# DB_Sensors-X02.net
KiCad netlist of a schematic drawn in Altium Designer
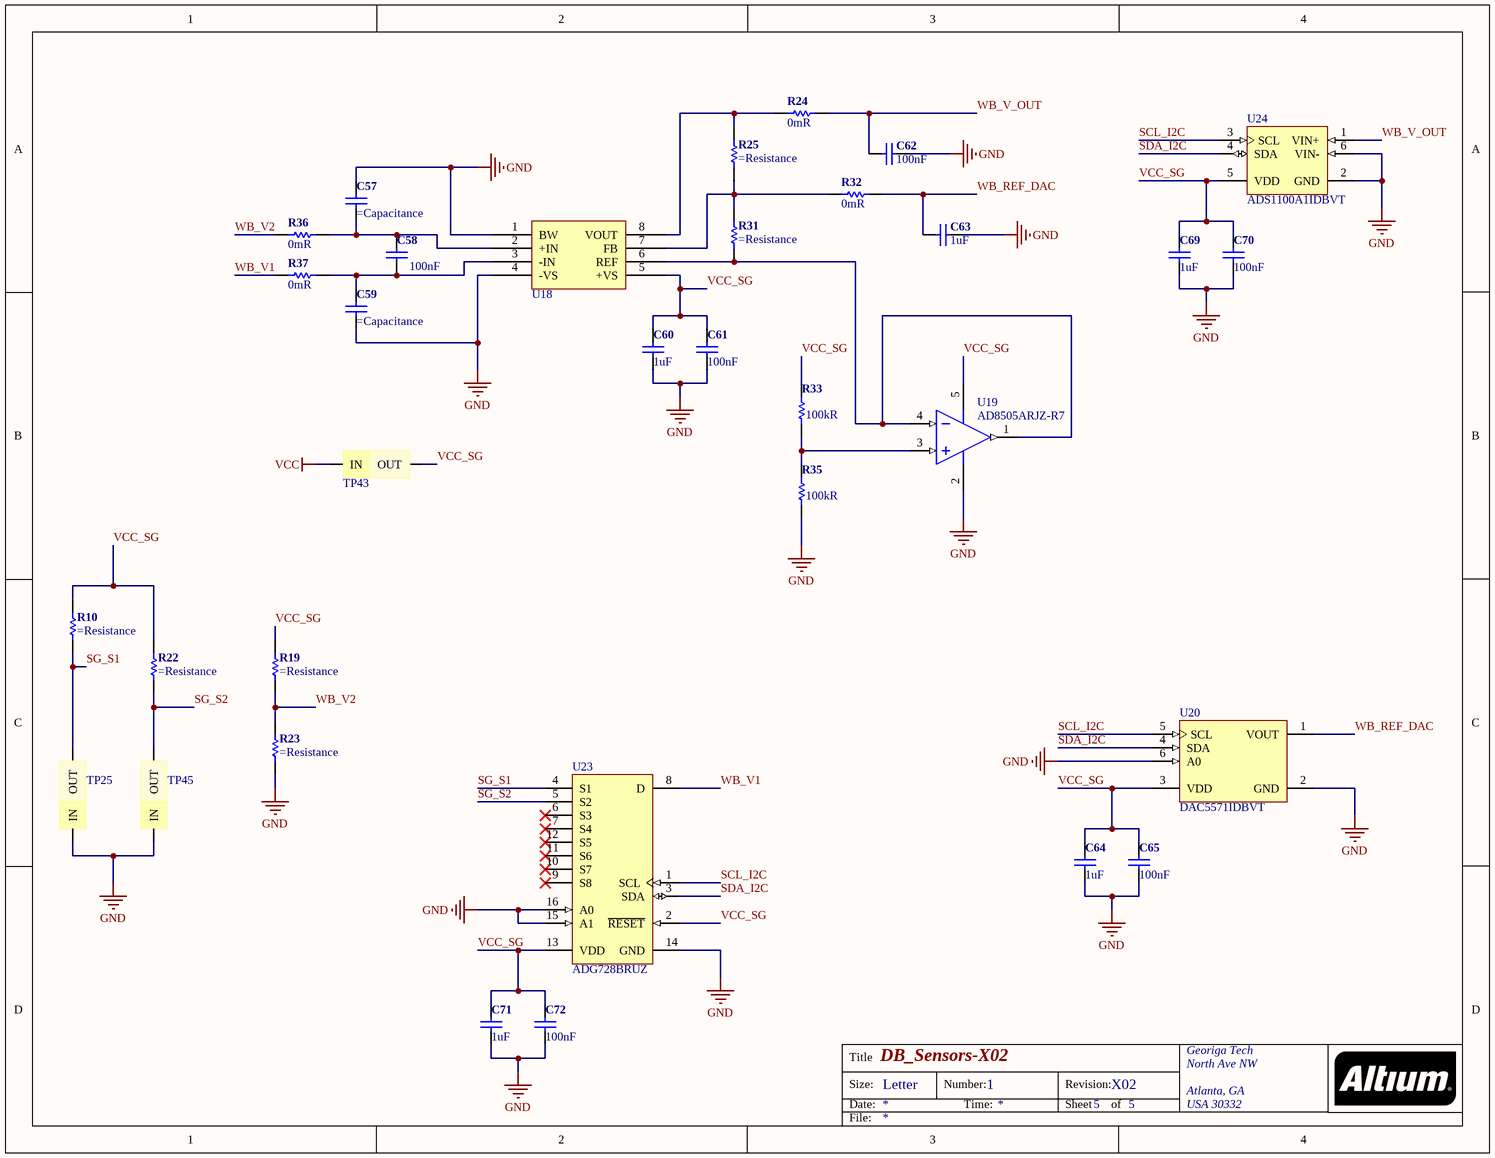
[diagram p0: DB_Sensors-X02.SchDoc]

(export (version "E")
  (design (tool "Eeschema 10.0.6"))
  (components
    (comp (ref "C57")
      (value "~")
      (footprint "C0402")
      (description "___ OHM ___ mW 0402(1005) SMD")
      (libsource (lib "DB-X02") (part "C-0402(1005)"))
    )
    (comp (ref "C58")
      (value "100nF")
      (footprint "C0402")
      (fields
        (field (name "MANUFACTURER") "Taiyo Yuden")
        (field (name "MANUFACTURER PART NUMBER") "TMK105BJ104KV-F")
        (field (name "TOLERANCE") "10%")
      )
      (libsource (lib "DB-X02") (part "C-0402(1005)"))
    )
    (comp (ref "C59")
      (value "~")
      (footprint "C0402")
      (description "___ OHM ___ mW 0402(1005) SMD")
      (libsource (lib "DB-X02") (part "C-0402(1005)"))
    )
    (comp (ref "C60")
      (value "1uF")
      (footprint "C0402")
      (fields
        (field (name "MANUFACTURER") "Yageo")
        (field (name "MANUFACTURER PART NUMBER") "CC0402MRX5R5BB105")
        (field (name "TOLERANCE") "20%")
      )
      (libsource (lib "DB-X02") (part "C-0402(1005)"))
    )
    (comp (ref "C61")
      (value "100nF")
      (footprint "C0402")
      (fields
        (field (name "MANUFACTURER") "Taiyo Yuden")
        (field (name "MANUFACTURER PART NUMBER") "TMK105BJ104KV-F")
        (field (name "TOLERANCE") "10%")
      )
      (libsource (lib "DB-X02") (part "C-0402(1005)"))
    )
    (comp (ref "C62")
      (value "100nF")
      (footprint "C0402")
      (fields
        (field (name "MANUFACTURER") "Taiyo Yuden")
        (field (name "MANUFACTURER PART NUMBER") "TMK105BJ104KV-F")
        (field (name "TOLERANCE") "10%")
      )
      (libsource (lib "DB-X02") (part "C-0402(1005)"))
    )
    (comp (ref "C63")
      (value "1uF")
      (footprint "C0402")
      (fields
        (field (name "MANUFACTURER") "Yageo")
        (field (name "MANUFACTURER PART NUMBER") "CC0402MRX5R5BB105")
        (field (name "TOLERANCE") "20%")
      )
      (libsource (lib "DB-X02") (part "C-0402(1005)"))
    )
    (comp (ref "C64")
      (value "1uF")
      (footprint "C0402")
      (fields
        (field (name "MANUFACTURER") "Yageo")
        (field (name "MANUFACTURER PART NUMBER") "CC0402MRX5R5BB105")
        (field (name "TOLERANCE") "20%")
      )
      (libsource (lib "DB-X02") (part "C-0402(1005)"))
    )
    (comp (ref "C65")
      (value "100nF")
      (footprint "C0402")
      (fields
        (field (name "MANUFACTURER") "Taiyo Yuden")
        (field (name "MANUFACTURER PART NUMBER") "TMK105BJ104KV-F")
        (field (name "TOLERANCE") "10%")
      )
      (libsource (lib "DB-X02") (part "C-0402(1005)"))
    )
    (comp (ref "C69")
      (value "1uF")
      (footprint "C0402")
      (fields
        (field (name "MANUFACTURER") "Yageo")
        (field (name "MANUFACTURER PART NUMBER") "CC0402MRX5R5BB105")
        (field (name "TOLERANCE") "20%")
      )
      (libsource (lib "DB-X02") (part "C-0402(1005)"))
    )
    (comp (ref "C70")
      (value "100nF")
      (footprint "C0402")
      (fields
        (field (name "MANUFACTURER") "Taiyo Yuden")
        (field (name "MANUFACTURER PART NUMBER") "TMK105BJ104KV-F")
        (field (name "TOLERANCE") "10%")
      )
      (libsource (lib "DB-X02") (part "C-0402(1005)"))
    )
    (comp (ref "C71")
      (value "1uF")
      (footprint "C0402")
      (fields
        (field (name "MANUFACTURER") "Yageo")
        (field (name "MANUFACTURER PART NUMBER") "CC0402MRX5R5BB105")
        (field (name "TOLERANCE") "20%")
      )
      (libsource (lib "DB-X02") (part "C-0402(1005)"))
    )
    (comp (ref "C72")
      (value "100nF")
      (footprint "C0402")
      (fields
        (field (name "MANUFACTURER") "Taiyo Yuden")
        (field (name "MANUFACTURER PART NUMBER") "TMK105BJ104KV-F")
        (field (name "TOLERANCE") "10%")
      )
      (libsource (lib "DB-X02") (part "C-0402(1005)"))
    )
    (comp (ref "R10")
      (value "~")
      (footprint "R0402")
      (description "___ OHM ___ mW 0402(1005) SMD")
      (libsource (lib "DB-X02") (part "R-0402(1005)"))
    )
    (comp (ref "R19")
      (value "~")
      (footprint "R0402")
      (description "___ OHM ___ mW 0402(1005) SMD")
      (libsource (lib "DB-X02") (part "R-0402(1005)"))
    )
    (comp (ref "R22")
      (value "~")
      (footprint "R0402")
      (description "___ OHM ___ mW 0402(1005) SMD")
      (libsource (lib "DB-X02") (part "R-0402(1005)"))
    )
    (comp (ref "R23")
      (value "~")
      (footprint "R0402")
      (description "___ OHM ___ mW 0402(1005) SMD")
      (libsource (lib "DB-X02") (part "R-0402(1005)"))
    )
    (comp (ref "R24")
      (value "0mR")
      (footprint "R0402")
      (description "Fixed Resistor, Metal Glaze/thick Film, 0.0625W, 0ohm, Surface Mount, 0402")
      (fields
        (field (name "MANUFACTURER") "Yageo")
        (field (name "MANUFACTURER PART NUMBER") "AC0402JR-070RL")
      )
      (libsource (lib "DB-X02") (part "R-0402(1005)"))
    )
    (comp (ref "R25")
      (value "~")
      (footprint "R0402")
      (description "___ OHM ___ mW 0402(1005) SMD")
      (libsource (lib "DB-X02") (part "R-0402(1005)"))
    )
    (comp (ref "R31")
      (value "~")
      (footprint "R0402")
      (description "___ OHM ___ mW 0402(1005) SMD")
      (libsource (lib "DB-X02") (part "R-0402(1005)"))
    )
    (comp (ref "R32")
      (value "0mR")
      (footprint "R0402")
      (description "Fixed Resistor, Metal Glaze/thick Film, 0.0625W, 0ohm, Surface Mount, 0402")
      (fields
        (field (name "MANUFACTURER") "Yageo")
        (field (name "MANUFACTURER PART NUMBER") "AC0402JR-070RL")
      )
      (libsource (lib "DB-X02") (part "R-0402(1005)"))
    )
    (comp (ref "R33")
      (value "100kR")
      (footprint "R0402")
      (fields
        (field (name "MANUFACTURER") "Yageo")
        (field (name "MANUFACTURER PART NUMBER") "AC0402FR-07100KL")
        (field (name "TOLERANCE") "1%")
      )
      (libsource (lib "DB-X02") (part "R-0402(1005)"))
    )
    (comp (ref "R35")
      (value "100kR")
      (footprint "R0402")
      (fields
        (field (name "MANUFACTURER") "Yageo")
        (field (name "MANUFACTURER PART NUMBER") "AC0402FR-07100KL")
        (field (name "TOLERANCE") "1%")
      )
      (libsource (lib "DB-X02") (part "R-0402(1005)"))
    )
    (comp (ref "R36")
      (value "0mR")
      (footprint "R0402")
      (description "Fixed Resistor, Metal Glaze/thick Film, 0.0625W, 0ohm, Surface Mount, 0402")
      (fields
        (field (name "MANUFACTURER") "Yageo")
        (field (name "MANUFACTURER PART NUMBER") "AC0402JR-070RL")
      )
      (libsource (lib "DB-X02") (part "R-0402(1005)"))
    )
    (comp (ref "R37")
      (value "0mR")
      (footprint "R0402")
      (description "Fixed Resistor, Metal Glaze/thick Film, 0.0625W, 0ohm, Surface Mount, 0402")
      (fields
        (field (name "MANUFACTURER") "Yageo")
        (field (name "MANUFACTURER PART NUMBER") "AC0402JR-070RL")
      )
      (libsource (lib "DB-X02") (part "R-0402(1005)"))
    )
    (comp (ref "TP25")
      (value "JUMPER")
      (footprint "JUMPER")
      (description "SHUNT LP W/HANDLE 2 POS 30AU")
      (fields
        (field (name "MANUFACTURER") "TE Connectivity")
        (field (name "MANUFACTURER PART NUMBER") "8815452")
      )
      (libsource (lib "DB-X02") (part "JUMPER"))
    )
    (comp (ref "TP43")
      (value "JUMPER")
      (footprint "JUMPER")
      (description "SHUNT LP W/HANDLE 2 POS 30AU")
      (fields
        (field (name "MANUFACTURER") "TE Connectivity")
        (field (name "MANUFACTURER PART NUMBER") "8815452")
      )
      (libsource (lib "") (part "JUMPER_1"))
    )
    (comp (ref "TP45")
      (value "JUMPER")
      (footprint "JUMPER")
      (description "SHUNT LP W/HANDLE 2 POS 30AU")
      (fields
        (field (name "MANUFACTURER") "TE Connectivity")
        (field (name "MANUFACTURER PART NUMBER") "8815452")
      )
      (libsource (lib "DB-X02") (part "JUMPER"))
    )
    (comp (ref "U18")
      (value "Instrumentation Amplifier")
      (footprint "8-MSOP")
      (description "Instrumentation Amplifier, 1 Func, 75uV Offset-Max, 0.2MHz Band Width, CMOS, PDSO8")
      (fields
        (field (name "MANUFACTURER") "Analog Devices")
        (field (name "MANUFACTURER PART NUMBER") "AD8237ARMZ-R7")
      )
      (libsource (lib "DB-X02") (part "AD8237"))
    )
    (comp (ref "U19")
      (value "AD8505ARJZ-R7")
      (footprint "ADI-RJ-5_N")
      (fields (field (name "MANUFACTURER") "Analog Devices"))
      (libsource (lib "Altium Content Vault") (part "ADI-ADxxxx-X-5"))
    )
    (comp (ref "U20")
      (value "DAC5571IDBVT")
      (footprint "TI-DBV6_M")
      (fields (field (name "MANUFACTURER") "Texas Instruments"))
      (libsource (lib "Altium Content Vault") (part "TI-DACX571DBV6"))
    )
    (comp (ref "U23")
      (value "ADG728BRUZ")
      (footprint "ADI-RU-16_M")
      (fields (field (name "MANUFACTURER") "Analog Devices"))
      (libsource (lib "Altium Content Vault") (part "ADI-ADG728-RU-16"))
    )
    (comp (ref "U24")
      (value "ADS1100A1IDBVT")
      (footprint "TI-DBV6_N")
      (description "Self-Calibrating, 16-Bit ADC, -40 to 85 degC, 6-pin SOT23 (DBV6), Green (RoHS & no Sb/Br)")
      (fields (field (name "MANUFACTURER") "Texas Instruments"))
      (libsource (lib "Altium Content Vault") (part "TI-ADS1XX0XDBV6"))
    )
  )
  (nets
    (net (code "1") (name "/SCL_I2C") (class "Default")
      (node (ref "U20") (pin "5") (pinfunction "SCL_5") (pintype "input"))
      (node (ref "U23") (pin "1") (pinfunction "SCL_1") (pintype "input"))
      (node (ref "U24") (pin "3") (pinfunction "SCL_3") (pintype "input"))
    )
    (net (code "2") (name "/SDA_I2C") (class "Default")
      (node (ref "U20") (pin "4") (pinfunction "SDA_4") (pintype "input"))
      (node (ref "U23") (pin "3") (pinfunction "SDA_3") (pintype "bidirectional"))
      (node (ref "U24") (pin "4") (pinfunction "SDA_4") (pintype "bidirectional"))
    )
    (net (code "3") (name "/SG_S1") (class "Default")
      (node (ref "R10") (pin "2") (pinfunction "2_2") (pintype "passive"))
      (node (ref "TP25") (pin "2") (pinfunction "OUT_2") (pintype "passive"))
      (node (ref "U23") (pin "4") (pinfunction "S1_4") (pintype "passive"))
    )
    (net (code "4") (name "/SG_S2") (class "Default")
      (node (ref "R22") (pin "2") (pinfunction "2_2") (pintype "passive"))
      (node (ref "TP45") (pin "2") (pinfunction "OUT_2") (pintype "passive"))
      (node (ref "U23") (pin "5") (pinfunction "S2_5") (pintype "passive"))
    )
    (net (code "5") (name "/VCC_SG") (class "Default")
      (node (ref "C60") (pin "1") (pinfunction "1_1") (pintype "passive"))
      (node (ref "C61") (pin "1") (pinfunction "1_1") (pintype "passive"))
      (node (ref "C64") (pin "1") (pinfunction "1_1") (pintype "passive"))
      (node (ref "C65") (pin "1") (pinfunction "1_1") (pintype "passive"))
      (node (ref "C69") (pin "1") (pinfunction "1_1") (pintype "passive"))
      (node (ref "C70") (pin "1") (pinfunction "1_1") (pintype "passive"))
      (node (ref "C71") (pin "1") (pinfunction "1_1") (pintype "passive"))
      (node (ref "C72") (pin "1") (pinfunction "1_1") (pintype "passive"))
      (node (ref "R10") (pin "1") (pinfunction "1_1") (pintype "passive"))
      (node (ref "R19") (pin "1") (pinfunction "1_1") (pintype "passive"))
      (node (ref "R22") (pin "1") (pinfunction "1_1") (pintype "passive"))
      (node (ref "R33") (pin "1") (pinfunction "1_1") (pintype "passive"))
      (node (ref "TP43") (pin "2") (pinfunction "OUT_2") (pintype "passive"))
      (node (ref "U18") (pin "5") (pinfunction "+VS_5") (pintype "passive"))
      (node (ref "U19") (pin "5") (pinfunction "+V_5") (pintype "power_in"))
      (node (ref "U20") (pin "3") (pinfunction "VDD_3") (pintype "power_in"))
      (node (ref "U23") (pin "13") (pinfunction "VDD_13") (pintype "power_in"))
      (node (ref "U23") (pin "2") (pinfunction "~{RESET}_2") (pintype "input"))
      (node (ref "U24") (pin "5") (pinfunction "VDD_5") (pintype "power_in"))
    )
    (net (code "6") (name "/WB_REF_DAC") (class "Default")
      (node (ref "C63") (pin "1") (pinfunction "1_1") (pintype "passive"))
      (node (ref "R32") (pin "2") (pinfunction "2_2") (pintype "passive"))
      (node (ref "U20") (pin "1") (pinfunction "VOUT_1") (pintype "tri_state"))
    )
    (net (code "7") (name "/WB_V1") (class "Default")
      (node (ref "R37") (pin "1") (pinfunction "1_1") (pintype "passive"))
      (node (ref "U23") (pin "8") (pinfunction "D_8") (pintype "passive"))
    )
    (net (code "8") (name "/WB_V2") (class "Default")
      (node (ref "R19") (pin "2") (pinfunction "2_2") (pintype "passive"))
      (node (ref "R23") (pin "1") (pinfunction "1_1") (pintype "passive"))
      (node (ref "R36") (pin "1") (pinfunction "1_1") (pintype "passive"))
    )
    (net (code "9") (name "/WB_V_OUT") (class "Default")
      (node (ref "C62") (pin "1") (pinfunction "1_1") (pintype "passive"))
      (node (ref "R24") (pin "2") (pinfunction "2_2") (pintype "passive"))
      (node (ref "U24") (pin "1") (pinfunction "VIN+_1") (pintype "input"))
    )
    (net (code "10") (name "GND") (class "Default")
      (node (ref "C57") (pin "1") (pinfunction "1_1") (pintype "passive"))
      (node (ref "C59") (pin "2") (pinfunction "2_2") (pintype "passive"))
      (node (ref "C60") (pin "2") (pinfunction "2_2") (pintype "passive"))
      (node (ref "C61") (pin "2") (pinfunction "2_2") (pintype "passive"))
      (node (ref "C62") (pin "2") (pinfunction "2_2") (pintype "passive"))
      (node (ref "C63") (pin "2") (pinfunction "2_2") (pintype "passive"))
      (node (ref "C64") (pin "2") (pinfunction "2_2") (pintype "passive"))
      (node (ref "C65") (pin "2") (pinfunction "2_2") (pintype "passive"))
      (node (ref "C69") (pin "2") (pinfunction "2_2") (pintype "passive"))
      (node (ref "C70") (pin "2") (pinfunction "2_2") (pintype "passive"))
      (node (ref "C71") (pin "2") (pinfunction "2_2") (pintype "passive"))
      (node (ref "C72") (pin "2") (pinfunction "2_2") (pintype "passive"))
      (node (ref "R23") (pin "2") (pinfunction "2_2") (pintype "passive"))
      (node (ref "R35") (pin "2") (pinfunction "2_2") (pintype "passive"))
      (node (ref "TP25") (pin "1") (pinfunction "IN_1") (pintype "passive"))
      (node (ref "TP45") (pin "1") (pinfunction "IN_1") (pintype "passive"))
      (node (ref "U18") (pin "1") (pinfunction "BW_1") (pintype "passive"))
      (node (ref "U18") (pin "4") (pinfunction "-VS_4") (pintype "passive"))
      (node (ref "U19") (pin "2") (pinfunction "-V_2") (pintype "power_in"))
      (node (ref "U20") (pin "2") (pinfunction "GND_2") (pintype "power_in"))
      (node (ref "U20") (pin "6") (pinfunction "A0_6") (pintype "input"))
      (node (ref "U23") (pin "14") (pinfunction "GND_14") (pintype "power_in"))
      (node (ref "U23") (pin "15") (pinfunction "A1_15") (pintype "input"))
      (node (ref "U23") (pin "16") (pinfunction "A0_16") (pintype "input"))
      (node (ref "U24") (pin "2") (pinfunction "GND_2") (pintype "power_in"))
      (node (ref "U24") (pin "6") (pinfunction "VIN-_6") (pintype "input"))
    )
    (net (code "11") (name "Net-(U18-+IN)") (class "Default")
      (node (ref "C57") (pin "2") (pinfunction "2_2") (pintype "passive"))
      (node (ref "C58") (pin "1") (pinfunction "1_1") (pintype "passive"))
      (node (ref "R36") (pin "2") (pinfunction "2_2") (pintype "passive"))
      (node (ref "U18") (pin "2") (pinfunction "+IN_2") (pintype "passive"))
    )
    (net (code "12") (name "Net-(U18--IN)") (class "Default")
      (node (ref "C58") (pin "2") (pinfunction "2_2") (pintype "passive"))
      (node (ref "C59") (pin "1") (pinfunction "1_1") (pintype "passive"))
      (node (ref "R37") (pin "2") (pinfunction "2_2") (pintype "passive"))
      (node (ref "U18") (pin "3") (pinfunction "-IN_3") (pintype "passive"))
    )
    (net (code "13") (name "Net-(U18-FB)") (class "Default")
      (node (ref "R25") (pin "1") (pinfunction "1_1") (pintype "passive"))
      (node (ref "R31") (pin "2") (pinfunction "2_2") (pintype "passive"))
      (node (ref "R32") (pin "1") (pinfunction "1_1") (pintype "passive"))
      (node (ref "U18") (pin "7") (pinfunction "FB_7") (pintype "passive"))
    )
    (net (code "14") (name "Net-(U18-REF)") (class "Default")
      (node (ref "R31") (pin "1") (pinfunction "1_1") (pintype "passive"))
      (node (ref "U18") (pin "6") (pinfunction "REF_6") (pintype "passive"))
      (node (ref "U19") (pin "1") (pinfunction "OUT_1") (pintype "output"))
      (node (ref "U19") (pin "4") (pinfunction "-IN_4") (pintype "input"))
    )
    (net (code "15") (name "Net-(U18-VOUT)") (class "Default")
      (node (ref "R24") (pin "1") (pinfunction "1_1") (pintype "passive"))
      (node (ref "R25") (pin "2") (pinfunction "2_2") (pintype "passive"))
      (node (ref "U18") (pin "8") (pinfunction "VOUT_8") (pintype "passive"))
    )
    (net (code "16") (name "Net-(U19-+IN)") (class "Default")
      (node (ref "R33") (pin "2") (pinfunction "2_2") (pintype "passive"))
      (node (ref "R35") (pin "1") (pinfunction "1_1") (pintype "passive"))
      (node (ref "U19") (pin "3") (pinfunction "+IN_3") (pintype "input"))
    )
    (net (code "17") (name "VCC") (class "Default")
      (node (ref "TP43") (pin "1") (pinfunction "IN_1") (pintype "passive"))
    )
    (net (code "18") (name "unconnected-(U23-S3-Pad6)") (class "Default")
      (node (ref "U23") (pin "6") (pinfunction "S3_6") (pintype "passive+no_connect"))
    )
    (net (code "19") (name "unconnected-(U23-S4-Pad7)") (class "Default")
      (node (ref "U23") (pin "7") (pinfunction "S4_7") (pintype "passive+no_connect"))
    )
    (net (code "20") (name "unconnected-(U23-S5-Pad12)") (class "Default")
      (node (ref "U23") (pin "12") (pinfunction "S5_12") (pintype "passive+no_connect"))
    )
    (net (code "21") (name "unconnected-(U23-S6-Pad11)") (class "Default")
      (node (ref "U23") (pin "11") (pinfunction "S6_11") (pintype "passive+no_connect"))
    )
    (net (code "22") (name "unconnected-(U23-S7-Pad10)") (class "Default")
      (node (ref "U23") (pin "10") (pinfunction "S7_10") (pintype "passive+no_connect"))
    )
    (net (code "23") (name "unconnected-(U23-S8-Pad9)") (class "Default")
      (node (ref "U23") (pin "9") (pinfunction "S8_9") (pintype "passive+no_connect"))
    )
  )
)
